# LAN9254_B_P1.net
KiCad netlist of a schematic drawn in Altium Designer
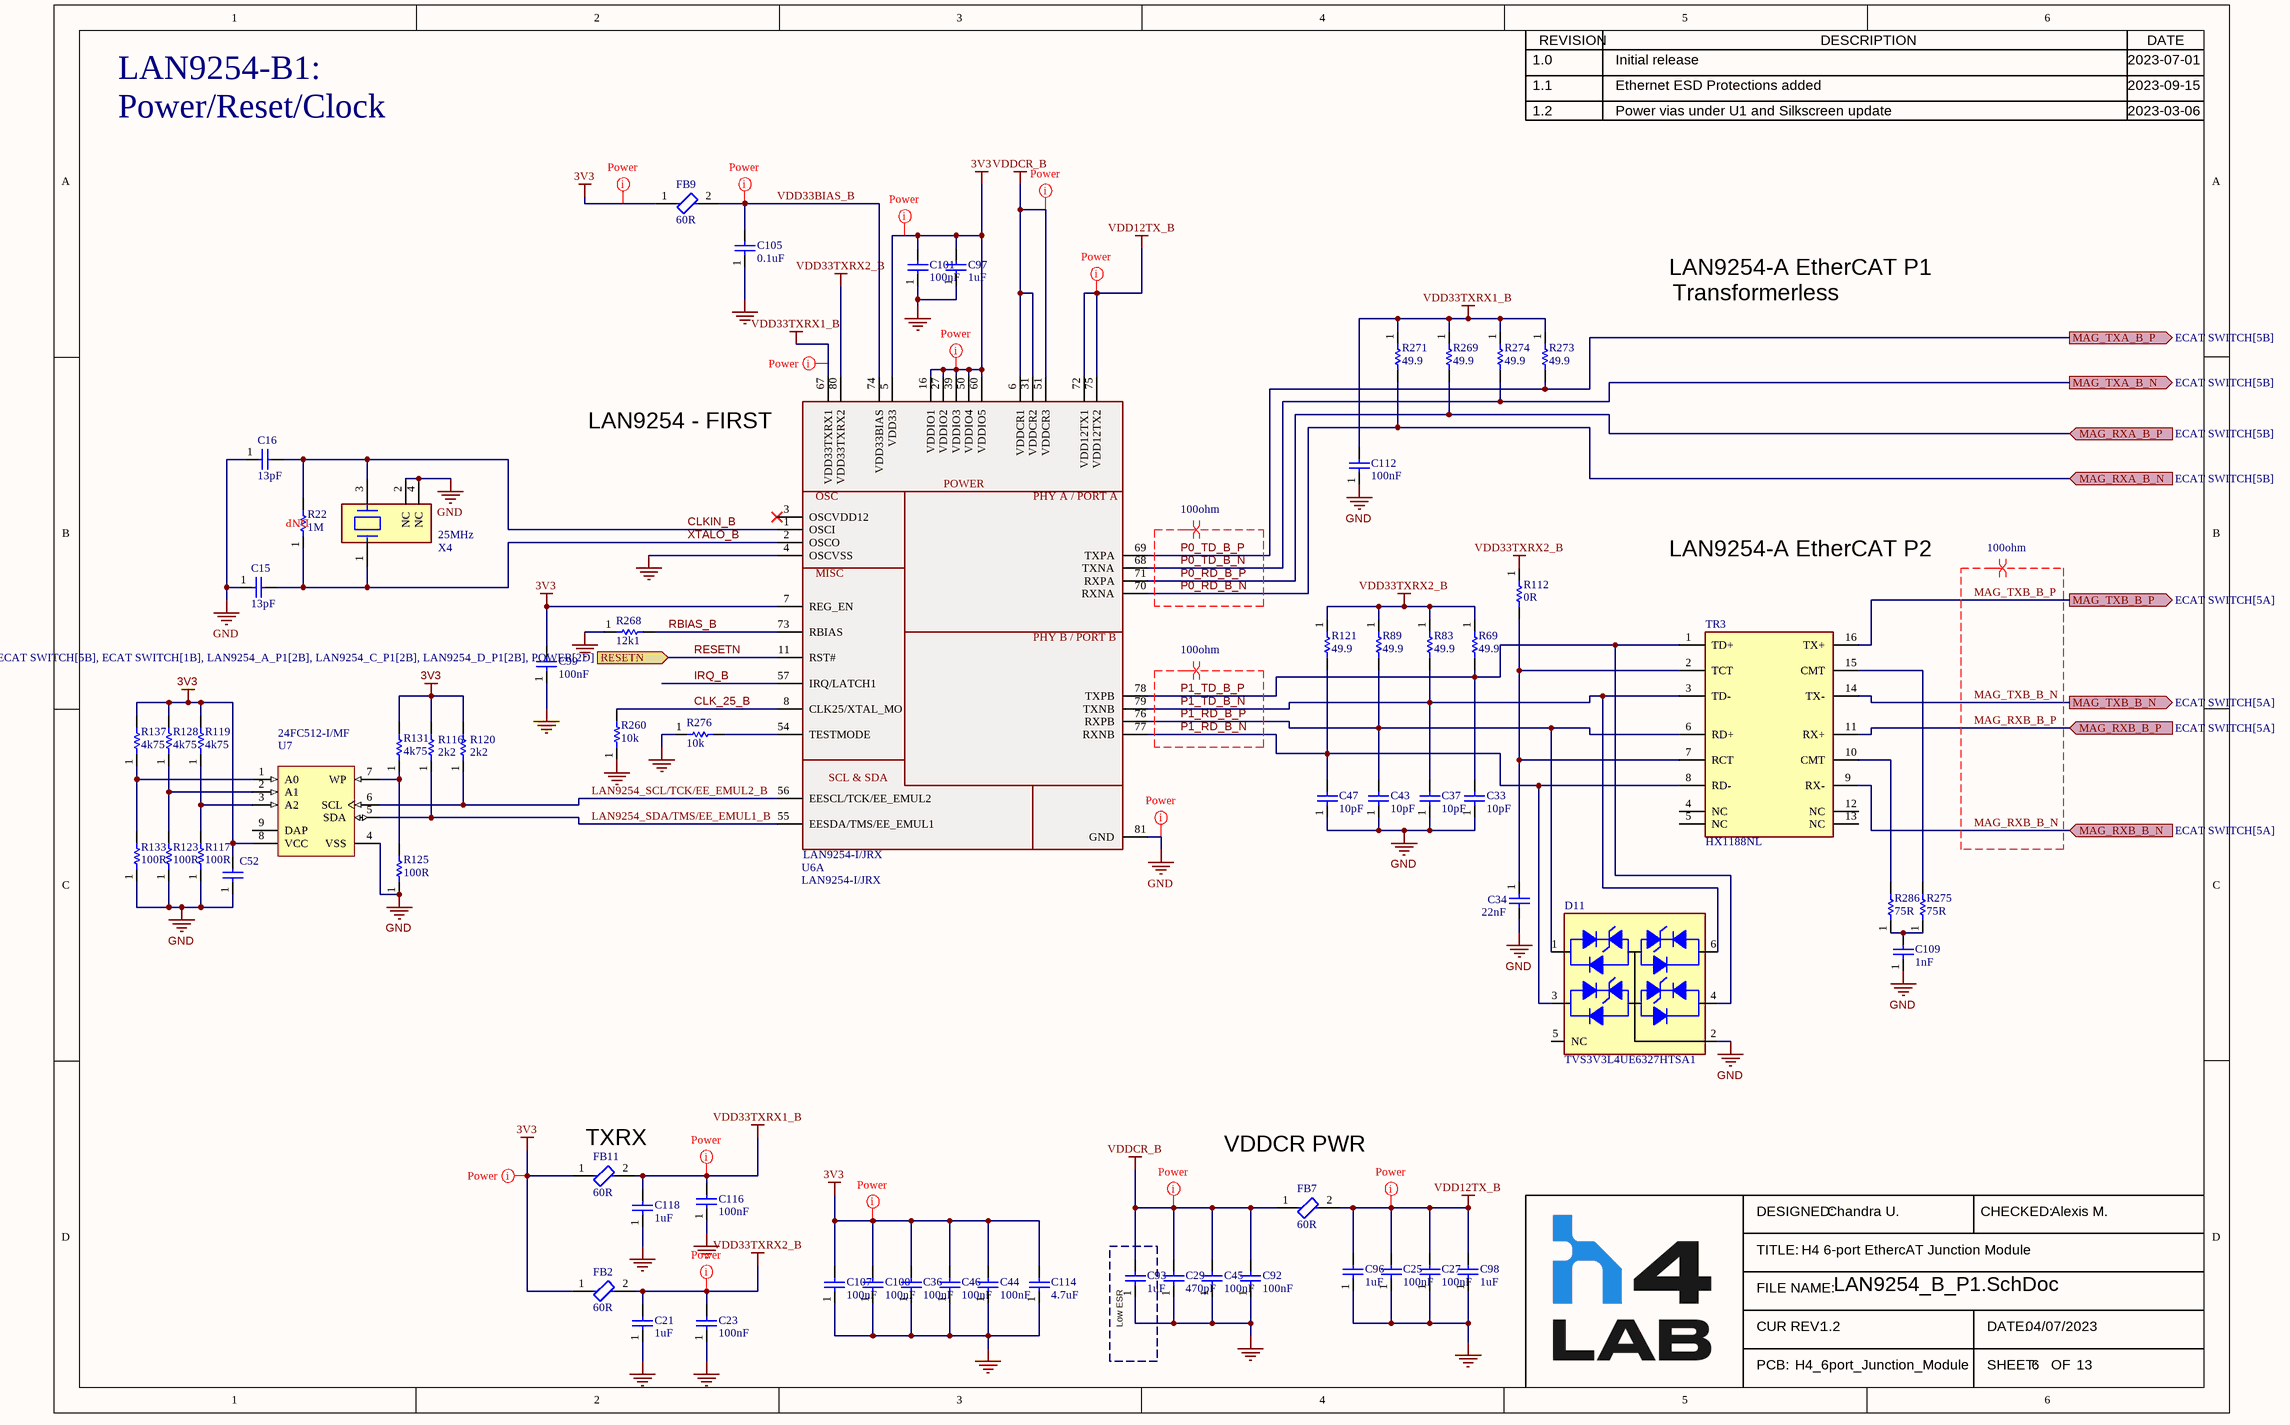
[diagram p0: LAN9254_B_P1.SchDoc]

(export (version "E")
  (design (tool "Eeschema 10.0.6"))
  (components
    (comp (ref "C15")
      (value "13pF")
      (footprint "0402_C")
      (description "Cap Ceramic Monolithic 13pF 50VDC 2% SMD Emboss T/R")
      (fields
        (field (name "MANUFACTURER") "Murata")
        (field (name "MANUFACTURER PART NUMBER") "GRM0225C1H130GA03L")
      )
      (libsource (lib "IHMC_Capacitors") (part "13pF_50V_0402_CAP_GRM0225C1H130GA03L"))
    )
    (comp (ref "C16")
      (value "13pF")
      (footprint "0402_C")
      (description "Cap Ceramic Monolithic 13pF 50VDC 2% SMD Emboss T/R")
      (fields
        (field (name "MANUFACTURER") "Murata")
        (field (name "MANUFACTURER PART NUMBER") "GRM0225C1H130GA03L")
      )
      (libsource (lib "IHMC_Capacitors") (part "13pF_50V_0402_CAP_GRM0225C1H130GA03L"))
    )
    (comp (ref "C21")
      (value "1uF")
      (footprint "CAPC1608X09N(0603)")
      (description "MLCC - SMD/SMT 25volts 1uF X5R 10%")
      (fields
        (field (name "MPN") "C0603C105K3PACTU")
        (field (name "VOLTAGE") "25VDC")
        (field (name "DRAWN BY") "TC")
      )
      (libsource (lib "IHMC_Altium_Lib") (part "1uF_25VDC_0603_Cap"))
    )
    (comp (ref "C23")
      (value "100nF")
      (footprint "CAPC1005X03N(0402)")
      (description "CAP CER 0.1UF 16V X7R 0402")
      (fields (field (name "MPN") "GRM155R71C104JA88D") (field (name "TOLERANCE") "5%"))
      (libsource (lib "IHMC_Altium_Lib") (part "100nF_16V_0402_CAP"))
    )
    (comp (ref "C25")
      (value "100nF")
      (footprint "CAPC1005X03N(0402)")
      (description "CAP CER 0.1UF 16V X7R 0402")
      (fields (field (name "MPN") "GRM155R71C104JA88D") (field (name "TOLERANCE") "5%"))
      (libsource (lib "IHMC_Altium_Lib") (part "100nF_16V_0402_CAP"))
    )
    (comp (ref "C27")
      (value "100nF")
      (footprint "CAPC1005X03N(0402)")
      (description "CAP CER 0.1UF 16V X7R 0402")
      (fields (field (name "MPN") "GRM155R71C104JA88D") (field (name "TOLERANCE") "5%"))
      (libsource (lib "IHMC_Altium_Lib") (part "100nF_16V_0402_CAP"))
    )
    (comp (ref "C29")
      (value "470pF")
      (footprint "CAPC1005X03N(0402)")
      (description "CAP CER 470PF 50V C0G/NP0 0402")
      (fields (field (name "MPN") "GCM1555C1H471JA16D") (field (name "VOLTAGE") "50V"))
      (libsource (lib "IHMC_Altium_Lib") (part "470pF_50V_0402_CAP"))
    )
    (comp (ref "C33")
      (value "10pF")
      (footprint "0402_C")
      (description "Cap Ceramic 10pF 50V C0G 5% SMD 0402 125°C Punched Paper T/R")
      (fields (field (name "TOLERANCE") "5%") (field (name "MANUFACTURER") "KEMET"))
      (libsource (lib "IHMC_Altium_Lib") (part "10pF_50V_0402_C0402C100J5GAC7411"))
    )
    (comp (ref "C34")
      (value "22nF")
      (footprint "CAPC1005X03N(0402)")
      (description "CAP CER 0.022UF 50V X7R 0402")
      (fields (field (name "MPN") "GCM155R71H223KA55D") (field (name "TOLERANCE") "10%"))
      (libsource (lib "IHMC_Capacitors") (part "22nF_50V_0402_CAP"))
    )
    (comp (ref "C36")
      (value "100nF")
      (footprint "CAPC1005X03N(0402)")
      (description "CAP CER 0.1UF 16V X7R 0402")
      (fields (field (name "MPN") "GRM155R71C104JA88D") (field (name "TOLERANCE") "5%"))
      (libsource (lib "IHMC_Altium_Lib") (part "100nF_16V_0402_CAP"))
    )
    (comp (ref "C37")
      (value "10pF")
      (footprint "0402_C")
      (description "Cap Ceramic 10pF 50V C0G 5% SMD 0402 125°C Punched Paper T/R")
      (fields (field (name "TOLERANCE") "5%") (field (name "MANUFACTURER") "KEMET"))
      (libsource (lib "IHMC_Altium_Lib") (part "10pF_50V_0402_C0402C100J5GAC7411"))
    )
    (comp (ref "C43")
      (value "10pF")
      (footprint "0402_C")
      (description "Cap Ceramic 10pF 50V C0G 5% SMD 0402 125°C Punched Paper T/R")
      (fields (field (name "TOLERANCE") "5%") (field (name "MANUFACTURER") "KEMET"))
      (libsource (lib "IHMC_Altium_Lib") (part "10pF_50V_0402_C0402C100J5GAC7411"))
    )
    (comp (ref "C44")
      (value "100nF")
      (footprint "CAPC1005X03N(0402)")
      (description "CAP CER 0.1UF 16V X7R 0402")
      (fields (field (name "MPN") "GRM155R71C104JA88D") (field (name "TOLERANCE") "5%"))
      (libsource (lib "IHMC_Altium_Lib") (part "100nF_16V_0402_CAP"))
    )
    (comp (ref "C45")
      (value "100nF")
      (footprint "CAPC1005X03N(0402)")
      (description "CAP CER 0.1UF 16V X7R 0402")
      (fields (field (name "MPN") "GRM155R71C104JA88D") (field (name "TOLERANCE") "5%"))
      (libsource (lib "IHMC_Altium_Lib") (part "100nF_16V_0402_CAP"))
    )
    (comp (ref "C46")
      (value "100nF")
      (footprint "CAPC1005X03N(0402)")
      (description "CAP CER 0.1UF 16V X7R 0402")
      (fields (field (name "MPN") "GRM155R71C104JA88D") (field (name "TOLERANCE") "5%"))
      (libsource (lib "IHMC_Altium_Lib") (part "100nF_16V_0402_CAP"))
    )
    (comp (ref "C47")
      (value "10pF")
      (footprint "0402_C")
      (description "Cap Ceramic 10pF 50V C0G 5% SMD 0402 125°C Punched Paper T/R")
      (fields (field (name "TOLERANCE") "5%") (field (name "MANUFACTURER") "KEMET"))
      (libsource (lib "IHMC_Altium_Lib") (part "10pF_50V_0402_C0402C100J5GAC7411"))
    )
    (comp (ref "C52")
      (value "GRM155R71C104JA88D")
      (footprint "CAPC1005X03N(0402)")
      (description "CAP CER 0.1UF 16V X7R 0402")
      (fields (field (name "TOLERANCE") "5%"))
      (libsource (lib "IHMC_Altium_Lib") (part "100nF_16V_0402_CAP"))
    )
    (comp (ref "C92")
      (value "100nF")
      (footprint "CAPC1005X03N(0402)")
      (description "CAP CER 0.1UF 16V X7R 0402")
      (fields (field (name "MPN") "GRM155R71C104JA88D") (field (name "TOLERANCE") "5%"))
      (libsource (lib "IHMC_Altium_Lib") (part "100nF_16V_0402_CAP"))
    )
    (comp (ref "C93")
      (value "1uF")
      (footprint "0603_C")
      (description "Multilayer Ceramic Capacitors (High dielectric type), 10V, 1 uF, ± 10 %, 0603, X5R, RoHS")
      (fields (field (name "TOLERANCE") "10%") (field (name "MANUFACTURER") "Taiyo Yuden"))
      (libsource (lib "IHMC_Capacitors") (part "1uF_10V_low_ESR_0603_LMK107BJ105KA-T"))
    )
    (comp (ref "C96")
      (value "1uF")
      (footprint "CAPC1608X09N(0603)")
      (description "MLCC - SMD/SMT 25volts 1uF X5R 10%")
      (fields
        (field (name "MPN") "C0603C105K3PACTU")
        (field (name "VOLTAGE") "25VDC")
        (field (name "DRAWN BY") "TC")
      )
      (libsource (lib "IHMC_Altium_Lib") (part "1uF_25VDC_0603_Cap"))
    )
    (comp (ref "C97")
      (value "1uF")
      (footprint "0603_C")
      (description "Multilayer Ceramic Capacitors (High dielectric type), 10V, 1 uF, ± 10 %, 0603, X5R, RoHS")
      (fields (field (name "TOLERANCE") "10%") (field (name "MANUFACTURER") "Taiyo Yuden"))
      (libsource (lib "IHMC_Capacitors") (part "1uF_10V_low_ESR_0603_LMK107BJ105KA-T"))
    )
    (comp (ref "C98")
      (value "1uF")
      (footprint "CAPC1608X09N(0603)")
      (description "MLCC - SMD/SMT 25volts 1uF X5R 10%")
      (fields
        (field (name "MPN") "C0603C105K3PACTU")
        (field (name "VOLTAGE") "25VDC")
        (field (name "DRAWN BY") "TC")
      )
      (libsource (lib "IHMC_Altium_Lib") (part "1uF_25VDC_0603_Cap"))
    )
    (comp (ref "C99")
      (value "100nF")
      (footprint "CAPC1005X03N(0402)")
      (description "CAP CER 0.1UF 16V X7R 0402")
      (fields (field (name "MPN") "GRM155R71C104JA88D") (field (name "TOLERANCE") "5%"))
      (libsource (lib "IHMC_Altium_Lib") (part "100nF_16V_0402_CAP"))
    )
    (comp (ref "C100")
      (value "100nF")
      (footprint "CAPC1005X03N(0402)")
      (description "CAP CER 0.1UF 16V X7R 0402")
      (fields (field (name "MPN") "GRM155R71C104JA88D") (field (name "TOLERANCE") "5%"))
      (libsource (lib "IHMC_Altium_Lib") (part "100nF_16V_0402_CAP"))
    )
    (comp (ref "C101")
      (value "100nF")
      (footprint "CAPC1005X03N(0402)")
      (description "CAP CER 0.1UF 16V X7R 0402")
      (fields (field (name "MPN") "GRM155R71C104JA88D") (field (name "TOLERANCE") "5%"))
      (libsource (lib "IHMC_Altium_Lib") (part "100nF_16V_0402_CAP"))
    )
    (comp (ref "C105")
      (value "0.1uF")
      (footprint "CAPC1608X09N(0603)")
      (description "CAP CER 0.1UF 100V X7R 0603")
      (fields (field (name "MPN") "CL10B104KC8NNNC") (field (name "TOLERANCE") "10%"))
      (libsource (lib "H4_6-port_EtherCAT_Junction_Module") (part "0.1uF_100V_0603_CAP"))
    )
    (comp (ref "C107")
      (value "100nF")
      (footprint "CAPC1005X03N(0402)")
      (description "CAP CER 0.1UF 16V X7R 0402")
      (fields (field (name "MPN") "GRM155R71C104JA88D") (field (name "TOLERANCE") "5%"))
      (libsource (lib "IHMC_Altium_Lib") (part "100nF_16V_0402_CAP"))
    )
    (comp (ref "C109")
      (value "1nF")
      (footprint "CAPC3216X16N(1206)")
      (description "CAP CER 1000PF 2KV X7R 1206")
      (fields (field (name "TOLERANCE") "10%") (field (name "MPN") "CC1206KKX7RDBB102"))
      (libsource (lib "IHMC_Altium_Lib") (part "1nF_2kV_1206_CAP"))
    )
    (comp (ref "C112")
      (value "100nF")
      (footprint "CAPC1005X03N(0402)")
      (description "CAP CER 0.1UF 16V X7R 0402")
      (fields (field (name "TOLERANCE") "5%") (field (name "MPN") "GRM155R71C104JA88D"))
      (libsource (lib "IHMC_Altium_Lib") (part "100nF_16V_0402_CAP"))
    )
    (comp (ref "C114")
      (value "4.7uF")
      (footprint "CAPC3216X16N(1206)")
      (description "CAP CER 4.7UF 50V X7R 1206")
      (fields (field (name "MPN") "CL31B475KBHNNNE") (field (name "TOLERANCE") "10%"))
      (libsource (lib "IHMC_Altium_Lib") (part "4.7uF_50V_1206_CAP"))
    )
    (comp (ref "C116")
      (value "100nF")
      (footprint "CAPC1005X03N(0402)")
      (description "CAP CER 0.1UF 16V X7R 0402")
      (fields (field (name "MPN") "GRM155R71C104JA88D") (field (name "TOLERANCE") "5%"))
      (libsource (lib "IHMC_Altium_Lib") (part "100nF_16V_0402_CAP"))
    )
    (comp (ref "C118")
      (value "1uF")
      (footprint "CAPC1608X09N(0603)")
      (description "MLCC - SMD/SMT 25volts 1uF X5R 10%")
      (fields
        (field (name "MPN") "C0603C105K3PACTU")
        (field (name "VOLTAGE") "25VDC")
        (field (name "DRAWN BY") "TC")
      )
      (libsource (lib "IHMC_Altium_Lib") (part "1uF_25VDC_0603_Cap"))
    )
    (comp (ref "D11")
      (value "TVS3V3L4UE6327HTSA1")
      (footprint "FP-SOT457-MFG")
      (description "Trans Voltage Suppressor Diode, 3.3V V(RWM), Unidirectional, 4 Element, Silicon")
      (fields (field (name "MANUFACTURER") "Infineon"))
      (libsource (lib "IHMC_Altium_Lib") (part "TVS_DIODE_ETHERCAT_PHY_7.7V_20A_TVS3V3L4UE6327HTSA1"))
    )
    (comp (ref "FB2")
      (value "BKP2125HS600-T")
      (footprint "FP-BKP2125-IPC_C")
      (fields
        (field (name "TOLERANCE") "25%")
        (field (name "MANUFACTURER") "Taiyo Yuden")
        (field (name "IMPEDANCE") "60R")
      )
      (libsource (lib "IHMC_Altium_Lib") (part "60R_100Mhz_0805_3A"))
    )
    (comp (ref "FB7")
      (value "BKP2125HS600-T")
      (footprint "FP-BKP2125-IPC_C")
      (fields
        (field (name "TOLERANCE") "25%")
        (field (name "MANUFACTURER") "Taiyo Yuden")
        (field (name "IMPEDANCE") "60R")
      )
      (libsource (lib "IHMC_Altium_Lib") (part "60R_100Mhz_0805_3A"))
    )
    (comp (ref "FB9")
      (value "BKP2125HS600-T")
      (footprint "FP-BKP2125-IPC_C")
      (fields
        (field (name "TOLERANCE") "25%")
        (field (name "MANUFACTURER") "Taiyo Yuden")
        (field (name "IMPEDANCE") "60R")
      )
      (libsource (lib "IHMC_Altium_Lib") (part "60R_100Mhz_0805_3A"))
    )
    (comp (ref "FB11")
      (value "BKP2125HS600-T")
      (footprint "FP-BKP2125-IPC_C")
      (fields
        (field (name "TOLERANCE") "25%")
        (field (name "MANUFACTURER") "Taiyo Yuden")
        (field (name "IMPEDANCE") "60R")
      )
      (libsource (lib "IHMC_Altium_Lib") (part "60R_100Mhz_0805_3A"))
    )
    (comp (ref "R22")
      (value "1M")
      (footprint "RESC1608X09N(0603)")
      (description "RES SMD 1M OHM 1% 1/10W 0603")
      (fields (field (name "MPN") "RC0603FR-071ML") (field (name "TOLERANCE") "1%"))
      (libsource (lib "IHMC_Altium_Lib") (part "1M_1/10W_RES_0603"))
    )
    (comp (ref "R69")
      (value "49.9")
      (footprint "RESC1005X06N(0402)")
      (description "RES SMD 49.9 OHM 1% 1/16W 0402")
      (fields
        (field (name "MPN") "CRCW040249R9FKED")
        (field (name "TOLERANCE") "1%")
        (field (name "DRAWN BY") "TC")
      )
      (libsource (lib "IHMC_Altium_Lib") (part "49R9_1/10W_0402_RES"))
    )
    (comp (ref "R83")
      (value "49.9")
      (footprint "RESC1005X06N(0402)")
      (description "RES SMD 49.9 OHM 1% 1/16W 0402")
      (fields
        (field (name "MPN") "CRCW040249R9FKED")
        (field (name "TOLERANCE") "1%")
        (field (name "DRAWN BY") "TC")
      )
      (libsource (lib "IHMC_Altium_Lib") (part "49R9_1/10W_0402_RES"))
    )
    (comp (ref "R89")
      (value "49.9")
      (footprint "RESC1005X06N(0402)")
      (description "RES SMD 49.9 OHM 1% 1/16W 0402")
      (fields
        (field (name "MPN") "CRCW040249R9FKED")
        (field (name "TOLERANCE") "1%")
        (field (name "DRAWN BY") "TC")
      )
      (libsource (lib "IHMC_Altium_Lib") (part "49R9_1/10W_0402_RES"))
    )
    (comp (ref "R112")
      (value "0R")
      (footprint "0402")
      (fields
        (field (name "MANUFACTURER") "Vishay Dale")
        (field (name "MANUFACTURER PART NUMBER") "RCS04020000Z0ED")
      )
      (libsource (lib "IHMC_Altium_Lib") (part "0R_1/5W_0402_RCS04020000Z0ED_RES"))
    )
    (comp (ref "R116")
      (value "2k2")
      (footprint "0402")
      (description "Vishay CRCW Series Thick Film Resistor 0402 Case 2.2k 5% 0.063W 200ppm/K")
      (fields (field (name "TOLERANCE") "5%") (field (name "MANUFACTURER") "Vishay Dale"))
      (libsource (lib "IHMC_Altium_Lib") (part "2k2_1/16_0402_CRCW04022K20JNED_RES"))
    )
    (comp (ref "R117")
      (value "100R")
      (footprint "0402")
      (description "Res Thick Film 0402 100 Ohm 1% 0.063W(1/16W) ±200ppm/C Pad SMD Automotive T/R")
      (fields
        (field (name "MANUFACTURER") "TE Connectivity")
        (field (name "MANUFACTURER PART NUMBER") "CRGCQ0402F100R")
      )
      (libsource (lib "IHMC_Altium_Lib") (part "100R_1/16_0402_RES"))
    )
    (comp (ref "R119")
      (value "4k75")
      (footprint "RESC1005X06N(0402)")
      (description "RES SMD 4.75K OHM 1% 1/16W 0402")
      (fields (field (name "MPN") "RC0402FR-074K75L") (field (name "POWER") "1/16"))
      (libsource (lib "IHMC_Altium_Lib") (part "4k75_1/16_0402_RES"))
    )
    (comp (ref "R120")
      (value "2k2")
      (footprint "0402")
      (description "Vishay CRCW Series Thick Film Resistor 0402 Case 2.2k 5% 0.063W 200ppm/K")
      (fields (field (name "TOLERANCE") "5%") (field (name "MANUFACTURER") "Vishay Dale"))
      (libsource (lib "IHMC_Altium_Lib") (part "2k2_1/16_0402_CRCW04022K20JNED_RES"))
    )
    (comp (ref "R121")
      (value "49.9")
      (footprint "RESC1005X06N(0402)")
      (description "RES SMD 49.9 OHM 1% 1/16W 0402")
      (fields
        (field (name "MPN") "CRCW040249R9FKED")
        (field (name "TOLERANCE") "1%")
        (field (name "DRAWN BY") "TC")
      )
      (libsource (lib "IHMC_Altium_Lib") (part "49R9_1/10W_0402_RES"))
    )
    (comp (ref "R123")
      (value "100R")
      (footprint "0402")
      (description "Res Thick Film 0402 100 Ohm 1% 0.063W(1/16W) ±200ppm/C Pad SMD Automotive T/R")
      (fields
        (field (name "MANUFACTURER") "TE Connectivity")
        (field (name "MANUFACTURER PART NUMBER") "CRGCQ0402F100R")
      )
      (libsource (lib "IHMC_Altium_Lib") (part "100R_1/16_0402_RES"))
    )
    (comp (ref "R125")
      (value "100R")
      (footprint "0402")
      (description "Res Thick Film 0402 100 Ohm 1% 0.063W(1/16W) ±200ppm/C Pad SMD Automotive T/R")
      (fields
        (field (name "MANUFACTURER") "TE Connectivity")
        (field (name "MANUFACTURER PART NUMBER") "CRGCQ0402F100R")
      )
      (libsource (lib "IHMC_Altium_Lib") (part "100R_1/16_0402_RES"))
    )
    (comp (ref "R128")
      (value "4k75")
      (footprint "RESC1005X06N(0402)")
      (description "RES SMD 4.75K OHM 1% 1/16W 0402")
      (fields (field (name "MPN") "RC0402FR-074K75L") (field (name "POWER") "1/16"))
      (libsource (lib "IHMC_Altium_Lib") (part "4k75_1/16_0402_RES"))
    )
    (comp (ref "R131")
      (value "4k75")
      (footprint "RESC1005X06N(0402)")
      (description "RES SMD 4.75K OHM 1% 1/16W 0402")
      (fields (field (name "MPN") "RC0402FR-074K75L") (field (name "POWER") "1/16"))
      (libsource (lib "IHMC_Altium_Lib") (part "4k75_1/16_0402_RES"))
    )
    (comp (ref "R133")
      (value "100R")
      (footprint "0402")
      (description "Res Thick Film 0402 100 Ohm 1% 0.063W(1/16W) ±200ppm/C Pad SMD Automotive T/R")
      (fields
        (field (name "MANUFACTURER") "TE Connectivity")
        (field (name "MANUFACTURER PART NUMBER") "CRGCQ0402F100R")
      )
      (libsource (lib "IHMC_Altium_Lib") (part "100R_1/16_0402_RES"))
    )
    (comp (ref "R137")
      (value "4k75")
      (footprint "RESC1005X06N(0402)")
      (description "RES SMD 4.75K OHM 1% 1/16W 0402")
      (fields (field (name "MPN") "RC0402FR-074K75L") (field (name "POWER") "1/16"))
      (libsource (lib "IHMC_Altium_Lib") (part "4k75_1/16_0402_RES"))
    )
    (comp (ref "R260")
      (value "10k")
      (footprint "RESC1005X06N(0402)")
      (description "RES SMD 10K OHM 1% 1/16W 0402")
      (fields (field (name "TOLERANCE") "1%") (field (name "POWER") "1/16W"))
      (libsource (lib "IHMC_Resistors") (part "10k_1/16W_0402_RES"))
    )
    (comp (ref "R268")
      (value "12k1")
      (footprint "RESC1005X06N(0402)")
      (description "RES SMD 12.1K OHM 1% 1/16W 0402")
      (fields (field (name "MPN") "RC0402FR-0712K1L") (field (name "TOLERANCE") "1%"))
      (libsource (lib "IHMC_Altium_Lib") (part "12k1_1/16W-0402_RES"))
    )
    (comp (ref "R269")
      (value "49.9")
      (footprint "RESC1005X06N(0402)")
      (description "RES SMD 49.9 OHM 1% 1/16W 0402")
      (fields
        (field (name "MPN") "CRCW040249R9FKED")
        (field (name "TOLERANCE") "1%")
        (field (name "DRAWN BY") "TC")
      )
      (libsource (lib "IHMC_Altium_Lib") (part "49R9_1/10W_0402_RES"))
    )
    (comp (ref "R271")
      (value "49.9")
      (footprint "RESC1005X06N(0402)")
      (description "RES SMD 49.9 OHM 1% 1/16W 0402")
      (fields
        (field (name "MPN") "CRCW040249R9FKED")
        (field (name "TOLERANCE") "1%")
        (field (name "DRAWN BY") "TC")
      )
      (libsource (lib "IHMC_Altium_Lib") (part "49R9_1/10W_0402_RES"))
    )
    (comp (ref "R273")
      (value "49.9")
      (footprint "RESC1005X06N(0402)")
      (description "RES SMD 49.9 OHM 1% 1/16W 0402")
      (fields
        (field (name "MPN") "CRCW040249R9FKED")
        (field (name "TOLERANCE") "1%")
        (field (name "DRAWN BY") "TC")
      )
      (libsource (lib "IHMC_Altium_Lib") (part "49R9_1/10W_0402_RES"))
    )
    (comp (ref "R274")
      (value "49.9")
      (footprint "RESC1005X06N(0402)")
      (description "RES SMD 49.9 OHM 1% 1/16W 0402")
      (fields
        (field (name "MPN") "CRCW040249R9FKED")
        (field (name "TOLERANCE") "1%")
        (field (name "DRAWN BY") "TC")
      )
      (libsource (lib "IHMC_Altium_Lib") (part "49R9_1/10W_0402_RES"))
    )
    (comp (ref "R275")
      (value "75R")
      (footprint "RESC1005X06N(0402)")
      (description "RES SMD 75 OHM 1% 1/16W 0402")
      (fields
        (field (name "MPN") "CRCW040275R0FKEDC")
        (field (name "TOLERANCE") "+/-1%")
        (field (name "DRAWN BY") "TC")
      )
      (libsource (lib "IHMC_Altium_Lib") (part "75R_1/10W_0402_RES"))
    )
    (comp (ref "R276")
      (value "10k")
      (footprint "RESC1005X06N(0402)")
      (description "RES SMD 10K OHM 1% 1/16W 0402")
      (fields (field (name "TOLERANCE") "1%") (field (name "POWER") "1/16W"))
      (libsource (lib "IHMC_Resistors") (part "10k_1/16W_0402_RES"))
    )
    (comp (ref "R286")
      (value "75R")
      (footprint "RESC1005X06N(0402)")
      (description "RES SMD 75 OHM 1% 1/16W 0402")
      (fields
        (field (name "MPN") "CRCW040275R0FKEDC")
        (field (name "TOLERANCE") "+/-1%")
        (field (name "DRAWN BY") "TC")
      )
      (libsource (lib "IHMC_Altium_Lib") (part "75R_1/10W_0402_RES"))
    )
    (comp (ref "TR3")
      (value "HX1188NL")
      (footprint "FP-HX1188NL-MFG")
      (description "Datacom Transformer, GENERAL PURPOSE Application(s), 1:1; 1:1")
      (fields (field (name "MANUFACTURER") "Pulse"))
      (libsource (lib "IHMC_Ethernet") (part "HX1188NL_TRANSFO_LAN_-40-85DEG"))
    )
    (comp (ref "U6")
      (value "LAN9254-I/JRX")
      (footprint "QFP50P1400X1400X120-81N")
      (description "2/3-PORT Ethercat Slave Controller With 32 Digios With Integrated Ethernet Phys")
      (fields (field (name "MANUFACTURER") "Microchip"))
      (libsource (lib "IHMC_Ethernet") (part "LAN9254-I/JRX"))
    )
    (comp (ref "U7")
      (value "24FC512-I/MF")
      (footprint "DFNS-MF8")
      (description "EEPROM Serial-2Wire 512K-bit 64K x 8 1.8V/2.5V/3.3V/5V 8-Pin DFN-S EP Tube")
      (fields (field (name "MANUFACTURER") "Microchip"))
      (libsource (lib "IHMC_Altium_Lib") (part "EEPROM_512kb_1MHz_24FC512-I/MF"))
    )
    (comp (ref "X4")
      (value "XRCGB25M000F3A00R0")
      (footprint "FP-XRCGB-MFG")
      (description "Crystal 25MHz ±30ppm (Tol) ±35ppm (Stability) 6pF 100Ohm Automotive 4-Pin SMD T/R")
      (fields (field (name "FREQUENCY") "25MHz") (field (name "MANUFACTURER") "Murata"))
      (libsource (lib "IHMC_Altium_Lib") (part "25MHz_Crystal_2016_35PPM_XRCGB25M000F3A00R0"))
    )
  )
  (nets
    (net (code "1") (name "/CLKIN_B") (class "Default")
      (node (ref "C16") (pin "2") (pinfunction "2_2") (pintype "passive"))
      (node (ref "R22") (pin "2") (pinfunction "2_2") (pintype "passive"))
      (node (ref "U6") (pin "1") (pinfunction "OSCI_1") (pintype "passive"))
      (node (ref "X4") (pin "3") (pintype "passive"))
    )
    (net (code "2") (name "/CLK_25_B") (class "Default")
      (node (ref "R260") (pin "2") (pinfunction "2_2") (pintype "passive"))
      (node (ref "U6") (pin "8") (pinfunction "CLK25/XTAL_MO_8") (pintype "passive"))
    )
    (net (code "3") (name "/IRQ_B") (class "Default")
      (node (ref "U6") (pin "57") (pinfunction "IRQ/LATCH1_57") (pintype "passive"))
    )
    (net (code "4") (name "/LAN9254_SCL{slash}TCK{slash}EE_EMUL2_B") (class "Default")
      (node (ref "R120") (pin "1") (pinfunction "1_1") (pintype "passive"))
      (node (ref "U6") (pin "56") (pinfunction "EESCL/TCK/EE_EMUL2_56") (pintype "passive"))
      (node (ref "U7") (pin "6") (pinfunction "SCL_6") (pintype "input"))
    )
    (net (code "5") (name "/LAN9254_SDA{slash}TMS{slash}EE_EMUL1_B") (class "Default")
      (node (ref "R116") (pin "1") (pinfunction "1_1") (pintype "passive"))
      (node (ref "U6") (pin "55") (pinfunction "EESDA/TMS/EE_EMUL1_55") (pintype "passive"))
      (node (ref "U7") (pin "5") (pinfunction "SDA_5") (pintype "bidirectional"))
    )
    (net (code "6") (name "/MAG_RXB_B_N") (class "Default")
      (node (ref "TR3") (pin "9") (pinfunction "RX-_9") (pintype "passive"))
    )
    (net (code "7") (name "/MAG_RXB_B_P") (class "Default")
      (node (ref "TR3") (pin "11") (pinfunction "RX+_11") (pintype "passive"))
    )
    (net (code "8") (name "/MAG_TXB_B_N") (class "Default")
      (node (ref "TR3") (pin "14") (pinfunction "TX-_14") (pintype "passive"))
    )
    (net (code "9") (name "/MAG_TXB_B_P") (class "Default")
      (node (ref "TR3") (pin "16") (pinfunction "TX+_16") (pintype "passive"))
    )
    (net (code "10") (name "/P0_RD_B_N") (class "Default")
      (node (ref "R271") (pin "2") (pinfunction "2_2") (pintype "passive"))
      (node (ref "U6") (pin "70") (pinfunction "RXNA_70") (pintype "passive"))
    )
    (net (code "11") (name "/P0_RD_B_P") (class "Default")
      (node (ref "R269") (pin "2") (pinfunction "2_2") (pintype "passive"))
      (node (ref "U6") (pin "71") (pinfunction "RXPA_71") (pintype "passive"))
    )
    (net (code "12") (name "/P0_TD_B_N") (class "Default")
      (node (ref "R274") (pin "2") (pinfunction "2_2") (pintype "passive"))
      (node (ref "U6") (pin "68") (pinfunction "TXNA_68") (pintype "passive"))
    )
    (net (code "13") (name "/P0_TD_B_P") (class "Default")
      (node (ref "R273") (pin "2") (pinfunction "2_2") (pintype "passive"))
      (node (ref "U6") (pin "69") (pinfunction "TXPA_69") (pintype "passive"))
    )
    (net (code "14") (name "/P1_RD_B_N") (class "Default")
      (node (ref "C47") (pin "2") (pinfunction "2_2") (pintype "passive"))
      (node (ref "D11") (pin "3") (pinfunction "3_3") (pintype "passive"))
      (node (ref "R121") (pin "2") (pinfunction "2_2") (pintype "passive"))
      (node (ref "TR3") (pin "8") (pinfunction "RD-_8") (pintype "passive"))
      (node (ref "U6") (pin "77") (pinfunction "RXNB_77") (pintype "passive"))
    )
    (net (code "15") (name "/P1_RD_B_P") (class "Default")
      (node (ref "C43") (pin "2") (pinfunction "2_2") (pintype "passive"))
      (node (ref "D11") (pin "1") (pinfunction "1_1") (pintype "passive"))
      (node (ref "R89") (pin "2") (pinfunction "2_2") (pintype "passive"))
      (node (ref "TR3") (pin "6") (pinfunction "RD+_6") (pintype "passive"))
      (node (ref "U6") (pin "76") (pinfunction "RXPB_76") (pintype "passive"))
    )
    (net (code "16") (name "/P1_TD_B_N") (class "Default")
      (node (ref "C37") (pin "2") (pinfunction "2_2") (pintype "passive"))
      (node (ref "D11") (pin "6") (pinfunction "6_6") (pintype "passive"))
      (node (ref "R83") (pin "2") (pinfunction "2_2") (pintype "passive"))
      (node (ref "TR3") (pin "3") (pinfunction "TD-_3") (pintype "passive"))
      (node (ref "U6") (pin "79") (pinfunction "TXNB_79") (pintype "passive"))
    )
    (net (code "17") (name "/P1_TD_B_P") (class "Default")
      (node (ref "C33") (pin "2") (pinfunction "2_2") (pintype "passive"))
      (node (ref "D11") (pin "4") (pinfunction "4_4") (pintype "passive"))
      (node (ref "R69") (pin "2") (pinfunction "2_2") (pintype "passive"))
      (node (ref "TR3") (pin "1") (pinfunction "TD+_1") (pintype "passive"))
      (node (ref "U6") (pin "78") (pinfunction "TXPB_78") (pintype "passive"))
    )
    (net (code "18") (name "/RBIAS_B") (class "Default")
      (node (ref "R268") (pin "2") (pinfunction "2_2") (pintype "passive"))
      (node (ref "U6") (pin "73") (pinfunction "RBIAS_73") (pintype "passive"))
    )
    (net (code "19") (name "/RESETN") (class "Default")
      (node (ref "U6") (pin "11") (pinfunction "RST#_11") (pintype "passive"))
    )
    (net (code "20") (name "/VDD33BIAS_B") (class "Default")
      (node (ref "C105") (pin "2") (pinfunction "2_2") (pintype "passive"))
      (node (ref "FB9") (pin "2") (pinfunction "2_2") (pintype "passive"))
      (node (ref "U6") (pin "74") (pinfunction "VDD33BIAS_74") (pintype "passive"))
    )
    (net (code "21") (name "/XTALO_B") (class "Default")
      (node (ref "C15") (pin "2") (pinfunction "2_2") (pintype "passive"))
      (node (ref "R22") (pin "1") (pinfunction "1_1") (pintype "passive"))
      (node (ref "U6") (pin "2") (pinfunction "OSCO_2") (pintype "passive"))
      (node (ref "X4") (pin "1") (pintype "passive"))
    )
    (net (code "22") (name "3V3") (class "Default")
      (node (ref "C100") (pin "2") (pinfunction "2_2") (pintype "passive"))
      (node (ref "C101") (pin "2") (pinfunction "2_2") (pintype "passive"))
      (node (ref "C107") (pin "2") (pinfunction "2_2") (pintype "passive"))
      (node (ref "C114") (pin "2") (pinfunction "2_2") (pintype "passive"))
      (node (ref "C36") (pin "2") (pinfunction "2_2") (pintype "passive"))
      (node (ref "C44") (pin "2") (pinfunction "2_2") (pintype "passive"))
      (node (ref "C46") (pin "2") (pinfunction "2_2") (pintype "passive"))
      (node (ref "C52") (pin "2") (pinfunction "2_2") (pintype "passive"))
      (node (ref "C97") (pin "2") (pinfunction "2_2") (pintype "passive"))
      (node (ref "C99") (pin "2") (pinfunction "2_2") (pintype "passive"))
      (node (ref "FB11") (pin "1") (pinfunction "1_1") (pintype "passive"))
      (node (ref "FB2") (pin "1") (pinfunction "1_1") (pintype "passive"))
      (node (ref "FB9") (pin "1") (pinfunction "1_1") (pintype "passive"))
      (node (ref "R116") (pin "2") (pinfunction "2_2") (pintype "passive"))
      (node (ref "R119") (pin "2") (pinfunction "2_2") (pintype "passive"))
      (node (ref "R120") (pin "2") (pinfunction "2_2") (pintype "passive"))
      (node (ref "R128") (pin "2") (pinfunction "2_2") (pintype "passive"))
      (node (ref "R131") (pin "2") (pinfunction "2_2") (pintype "passive"))
      (node (ref "R137") (pin "2") (pinfunction "2_2") (pintype "passive"))
      (node (ref "U6") (pin "16") (pinfunction "VDDIO1_16") (pintype "passive"))
      (node (ref "U6") (pin "27") (pinfunction "VDDIO2_27") (pintype "passive"))
      (node (ref "U6") (pin "39") (pinfunction "VDDIO3_39") (pintype "passive"))
      (node (ref "U6") (pin "5") (pinfunction "VDD33_5") (pintype "passive"))
      (node (ref "U6") (pin "50") (pinfunction "VDDIO4_50") (pintype "passive"))
      (node (ref "U6") (pin "60") (pinfunction "VDDIO5_60") (pintype "passive"))
      (node (ref "U6") (pin "7") (pinfunction "REG_EN_7") (pintype "passive"))
      (node (ref "U7") (pin "8") (pinfunction "VCC_8") (pintype "power_in"))
    )
    (net (code "23") (name "GND") (class "Default")
      (node (ref "C100") (pin "1") (pinfunction "1_1") (pintype "passive"))
      (node (ref "C101") (pin "1") (pinfunction "1_1") (pintype "passive"))
      (node (ref "C105") (pin "1") (pinfunction "1_1") (pintype "passive"))
      (node (ref "C107") (pin "1") (pinfunction "1_1") (pintype "passive"))
      (node (ref "C109") (pin "1") (pinfunction "1_1") (pintype "passive"))
      (node (ref "C112") (pin "1") (pinfunction "1_1") (pintype "passive"))
      (node (ref "C114") (pin "1") (pinfunction "1_1") (pintype "passive"))
      (node (ref "C116") (pin "1") (pinfunction "1_1") (pintype "passive"))
      (node (ref "C118") (pin "1") (pinfunction "1_1") (pintype "passive"))
      (node (ref "C15") (pin "1") (pinfunction "1_1") (pintype "passive"))
      (node (ref "C16") (pin "1") (pinfunction "1_1") (pintype "passive"))
      (node (ref "C21") (pin "1") (pinfunction "1_1") (pintype "passive"))
      (node (ref "C23") (pin "1") (pinfunction "1_1") (pintype "passive"))
      (node (ref "C25") (pin "1") (pinfunction "1_1") (pintype "passive"))
      (node (ref "C27") (pin "1") (pinfunction "1_1") (pintype "passive"))
      (node (ref "C29") (pin "1") (pinfunction "1_1") (pintype "passive"))
      (node (ref "C33") (pin "1") (pinfunction "1_1") (pintype "passive"))
      (node (ref "C34") (pin "2") (pinfunction "2_2") (pintype "passive"))
      (node (ref "C36") (pin "1") (pinfunction "1_1") (pintype "passive"))
      (node (ref "C37") (pin "1") (pinfunction "1_1") (pintype "passive"))
      (node (ref "C43") (pin "1") (pinfunction "1_1") (pintype "passive"))
      (node (ref "C44") (pin "1") (pinfunction "1_1") (pintype "passive"))
      (node (ref "C45") (pin "1") (pinfunction "1_1") (pintype "passive"))
      (node (ref "C46") (pin "1") (pinfunction "1_1") (pintype "passive"))
      (node (ref "C47") (pin "1") (pinfunction "1_1") (pintype "passive"))
      (node (ref "C52") (pin "1") (pinfunction "1_1") (pintype "passive"))
      (node (ref "C92") (pin "1") (pinfunction "1_1") (pintype "passive"))
      (node (ref "C93") (pin "1") (pinfunction "1_1") (pintype "passive"))
      (node (ref "C96") (pin "1") (pinfunction "1_1") (pintype "passive"))
      (node (ref "C97") (pin "1") (pinfunction "1_1") (pintype "passive"))
      (node (ref "C98") (pin "1") (pinfunction "1_1") (pintype "passive"))
      (node (ref "C99") (pin "1") (pinfunction "1_1") (pintype "passive"))
      (node (ref "D11") (pin "2") (pinfunction "GND_2") (pintype "power_in"))
      (node (ref "R117") (pin "1") (pinfunction "1_1") (pintype "passive"))
      (node (ref "R123") (pin "1") (pinfunction "1_1") (pintype "passive"))
      (node (ref "R125") (pin "1") (pinfunction "1_1") (pintype "passive"))
      (node (ref "R133") (pin "1") (pinfunction "1_1") (pintype "passive"))
      (node (ref "R260") (pin "1") (pinfunction "1_1") (pintype "passive"))
      (node (ref "R268") (pin "1") (pinfunction "1_1") (pintype "passive"))
      (node (ref "R276") (pin "1") (pinfunction "1_1") (pintype "passive"))
      (node (ref "U6") (pin "4") (pinfunction "OSCVSS_4") (pintype "passive"))
      (node (ref "U6") (pin "81") (pinfunction "GND_81") (pintype "passive"))
      (node (ref "U7") (pin "4") (pinfunction "VSS_4") (pintype "power_in"))
      (node (ref "X4") (pin "2") (pinfunction "NC_2") (pintype "passive"))
      (node (ref "X4") (pin "4") (pinfunction "NC_4") (pintype "passive"))
    )
    (net (code "24") (name "Net-(C109-Pad2)") (class "Default")
      (node (ref "C109") (pin "2") (pinfunction "2_2") (pintype "passive"))
      (node (ref "R275") (pin "1") (pinfunction "1_1") (pintype "passive"))
      (node (ref "R286") (pin "1") (pinfunction "1_1") (pintype "passive"))
    )
    (net (code "25") (name "Net-(R275-Pad2)") (class "Default")
      (node (ref "R275") (pin "2") (pinfunction "2_2") (pintype "passive"))
      (node (ref "TR3") (pin "15") (pinfunction "CMT_15") (pintype "passive"))
    )
    (net (code "26") (name "Net-(R286-Pad2)") (class "Default")
      (node (ref "R286") (pin "2") (pinfunction "2_2") (pintype "passive"))
      (node (ref "TR3") (pin "10") (pinfunction "CMT_10") (pintype "passive"))
    )
    (net (code "27") (name "Net-(TR3-RCT)") (class "Default")
      (node (ref "C34") (pin "1") (pinfunction "1_1") (pintype "passive"))
      (node (ref "R112") (pin "2") (pinfunction "2_2") (pintype "passive"))
      (node (ref "TR3") (pin "2") (pinfunction "TCT_2") (pintype "passive"))
      (node (ref "TR3") (pin "7") (pinfunction "RCT_7") (pintype "passive"))
    )
    (net (code "28") (name "Net-(U6A-TESTMODE)") (class "Default")
      (node (ref "R276") (pin "2") (pinfunction "2_2") (pintype "passive"))
      (node (ref "U6") (pin "54") (pinfunction "TESTMODE_54") (pintype "passive"))
    )
    (net (code "29") (name "Net-(U7-A0)") (class "Default")
      (node (ref "R133") (pin "2") (pinfunction "2_2") (pintype "passive"))
      (node (ref "R137") (pin "1") (pinfunction "1_1") (pintype "passive"))
      (node (ref "U7") (pin "1") (pinfunction "A0_1") (pintype "input"))
    )
    (net (code "30") (name "Net-(U7-A1)") (class "Default")
      (node (ref "R123") (pin "2") (pinfunction "2_2") (pintype "passive"))
      (node (ref "R128") (pin "1") (pinfunction "1_1") (pintype "passive"))
      (node (ref "U7") (pin "2") (pinfunction "A1_2") (pintype "input"))
    )
    (net (code "31") (name "Net-(U7-A2)") (class "Default")
      (node (ref "R117") (pin "2") (pinfunction "2_2") (pintype "passive"))
      (node (ref "R119") (pin "1") (pinfunction "1_1") (pintype "passive"))
      (node (ref "U7") (pin "3") (pinfunction "A2_3") (pintype "input"))
    )
    (net (code "32") (name "Net-(U7-WP)") (class "Default")
      (node (ref "R125") (pin "2") (pinfunction "2_2") (pintype "passive"))
      (node (ref "R131") (pin "1") (pinfunction "1_1") (pintype "passive"))
      (node (ref "U7") (pin "7") (pinfunction "WP_7") (pintype "input"))
    )
    (net (code "33") (name "VDD12TX_B") (class "Default")
      (node (ref "C25") (pin "2") (pinfunction "2_2") (pintype "passive"))
      (node (ref "C27") (pin "2") (pinfunction "2_2") (pintype "passive"))
      (node (ref "C96") (pin "2") (pinfunction "2_2") (pintype "passive"))
      (node (ref "C98") (pin "2") (pinfunction "2_2") (pintype "passive"))
      (node (ref "FB7") (pin "2") (pinfunction "2_2") (pintype "passive"))
      (node (ref "U6") (pin "72") (pinfunction "VDD12TX1_72") (pintype "passive"))
      (node (ref "U6") (pin "75") (pinfunction "VDD12TX2_75") (pintype "passive"))
    )
    (net (code "34") (name "VDD33TXRX1_B") (class "Default")
      (node (ref "C112") (pin "2") (pinfunction "2_2") (pintype "passive"))
      (node (ref "C116") (pin "2") (pinfunction "2_2") (pintype "passive"))
      (node (ref "C118") (pin "2") (pinfunction "2_2") (pintype "passive"))
      (node (ref "FB11") (pin "2") (pinfunction "2_2") (pintype "passive"))
      (node (ref "R269") (pin "1") (pinfunction "1_1") (pintype "passive"))
      (node (ref "R271") (pin "1") (pinfunction "1_1") (pintype "passive"))
      (node (ref "R273") (pin "1") (pinfunction "1_1") (pintype "passive"))
      (node (ref "R274") (pin "1") (pinfunction "1_1") (pintype "passive"))
      (node (ref "U6") (pin "67") (pinfunction "VDD33TXRX1_67") (pintype "passive"))
    )
    (net (code "35") (name "VDD33TXRX2_B") (class "Default")
      (node (ref "C21") (pin "2") (pinfunction "2_2") (pintype "passive"))
      (node (ref "C23") (pin "2") (pinfunction "2_2") (pintype "passive"))
      (node (ref "FB2") (pin "2") (pinfunction "2_2") (pintype "passive"))
      (node (ref "R112") (pin "1") (pinfunction "1_1") (pintype "passive"))
      (node (ref "R121") (pin "1") (pinfunction "1_1") (pintype "passive"))
      (node (ref "R69") (pin "1") (pinfunction "1_1") (pintype "passive"))
      (node (ref "R83") (pin "1") (pinfunction "1_1") (pintype "passive"))
      (node (ref "R89") (pin "1") (pinfunction "1_1") (pintype "passive"))
      (node (ref "U6") (pin "80") (pinfunction "VDD33TXRX2_80") (pintype "passive"))
    )
    (net (code "36") (name "VDDCR_B") (class "Default")
      (node (ref "C29") (pin "2") (pinfunction "2_2") (pintype "passive"))
      (node (ref "C45") (pin "2") (pinfunction "2_2") (pintype "passive"))
      (node (ref "C92") (pin "2") (pinfunction "2_2") (pintype "passive"))
      (node (ref "C93") (pin "2") (pinfunction "2_2") (pintype "passive"))
      (node (ref "FB7") (pin "1") (pinfunction "1_1") (pintype "passive"))
      (node (ref "U6") (pin "31") (pinfunction "VDDCR2_31") (pintype "passive"))
      (node (ref "U6") (pin "51") (pinfunction "VDDCR3_51") (pintype "passive"))
      (node (ref "U6") (pin "6") (pinfunction "VDDCR1_6") (pintype "passive"))
    )
    (net (code "37") (name "unconnected-(D11-NC-Pad5)") (class "Default")
      (node (ref "D11") (pin "5") (pinfunction "NC_5") (pintype "passive"))
    )
    (net (code "38") (name "unconnected-(TR3-NC-Pad4)") (class "Default")
      (node (ref "TR3") (pin "4") (pinfunction "NC_4") (pintype "passive"))
    )
    (net (code "39") (name "unconnected-(TR3-NC-Pad5)") (class "Default")
      (node (ref "TR3") (pin "5") (pinfunction "NC_5") (pintype "passive"))
    )
    (net (code "40") (name "unconnected-(TR3-NC-Pad12)") (class "Default")
      (node (ref "TR3") (pin "12") (pinfunction "NC_12") (pintype "passive"))
    )
    (net (code "41") (name "unconnected-(TR3-NC-Pad13)") (class "Default")
      (node (ref "TR3") (pin "13") (pinfunction "NC_13") (pintype "passive"))
    )
    (net (code "42") (name "unconnected-(U6A-OSCVDD12-Pad3)") (class "Default")
      (node (ref "U6") (pin "3") (pinfunction "OSCVDD12_3") (pintype "passive+no_connect"))
    )
    (net (code "43") (name "unconnected-(U7-DAP-Pad9)") (class "Default")
      (node (ref "U7") (pin "9") (pinfunction "DAP_9") (pintype "power_in"))
    )
  )
)
